# AS1324_imp.net
KiCad netlist of a schematic drawn in EAGLE
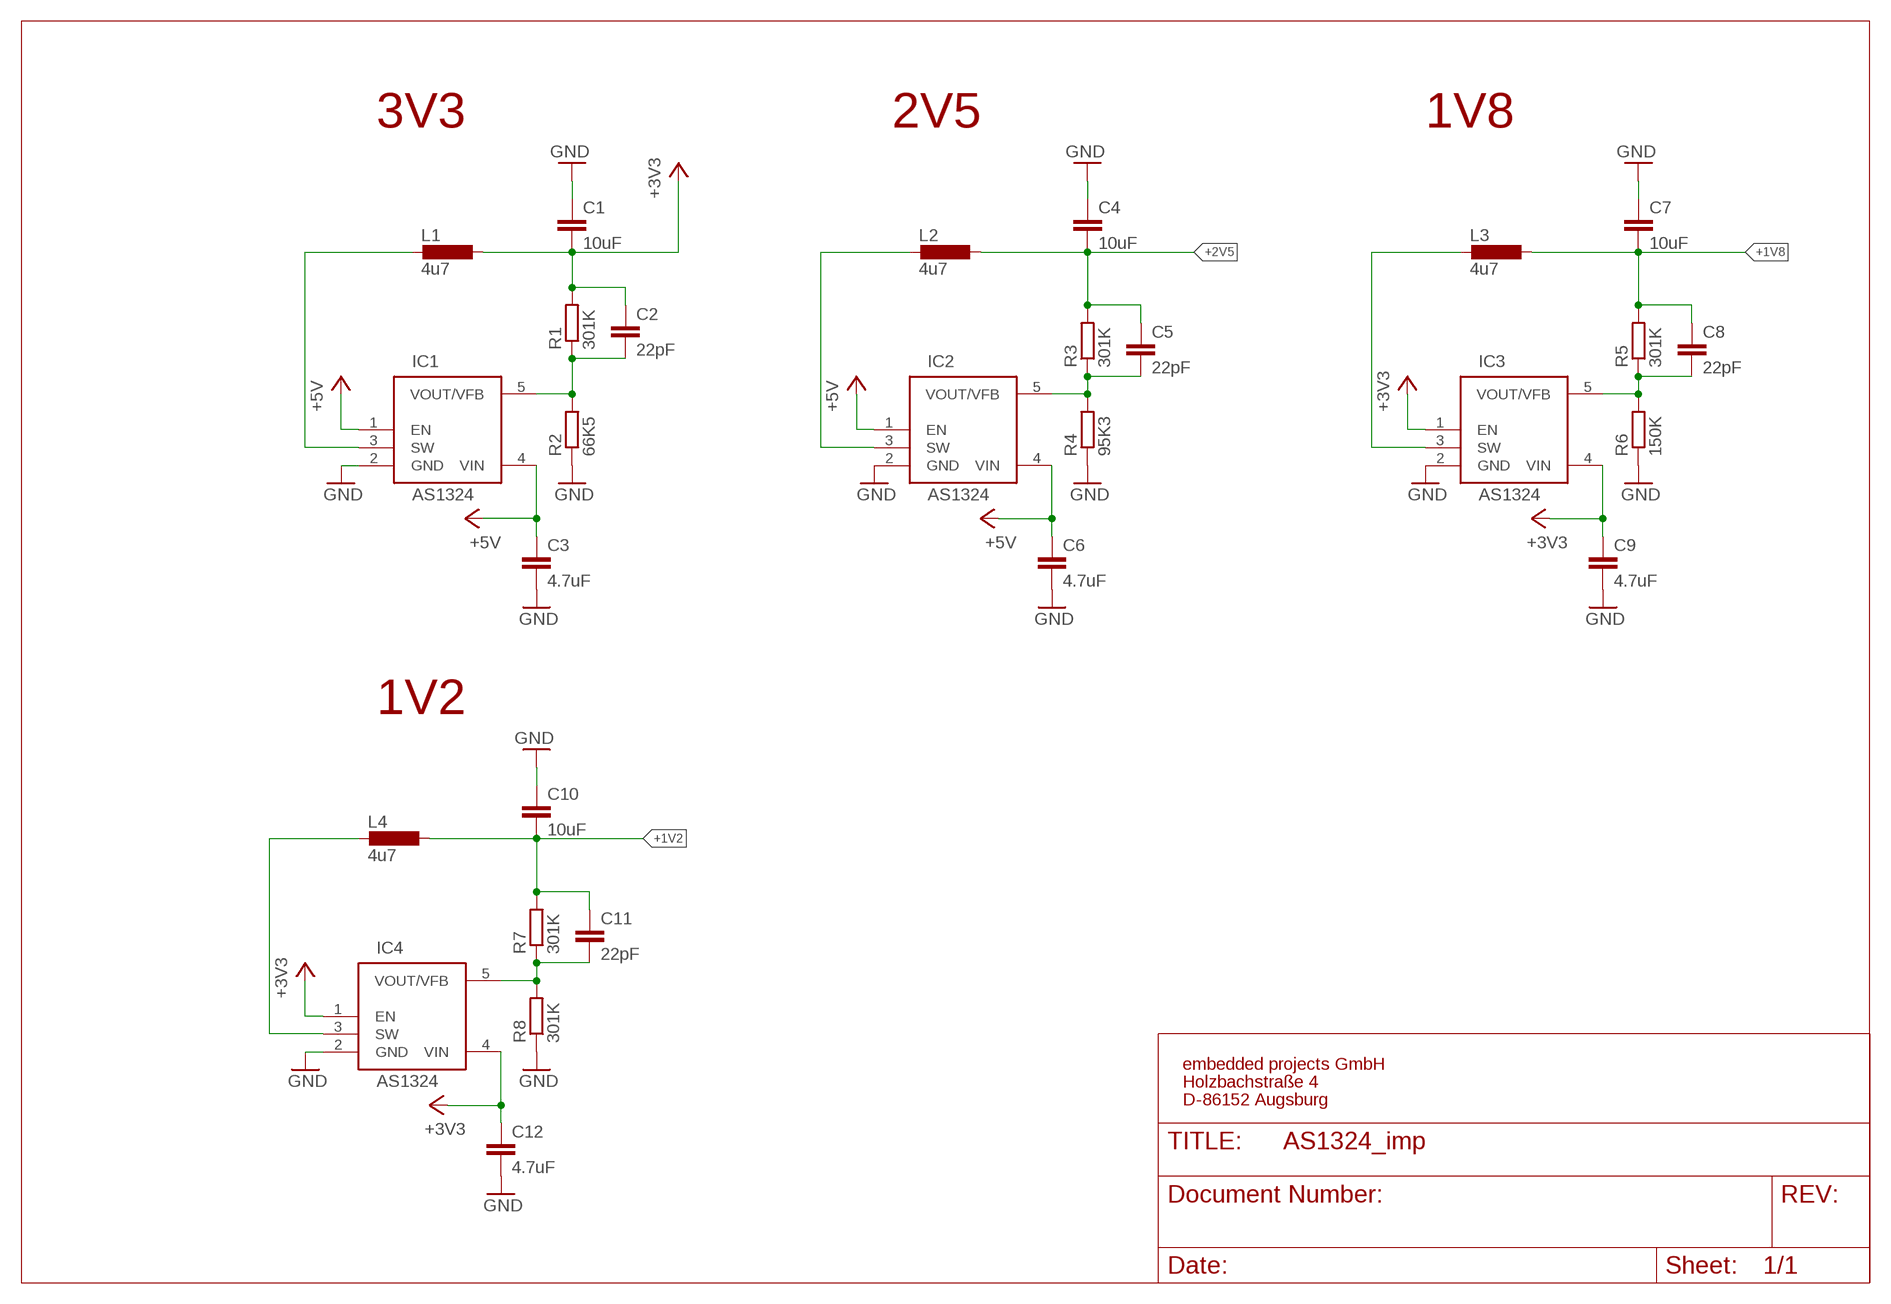
[diagram p0: schematic, sheet 1]

(export (version "E")
  (design (tool "Eeschema 10.0.6"))
  (components
    (comp (ref "C1")
      (value "10uF")
      (footprint "eagle-import:C0805")
      (libsource (lib "eagle-import") (part "C-EUC0805"))
    )
    (comp (ref "C2")
      (value "22pF")
      (footprint "eagle-import:C0805")
      (libsource (lib "eagle-import") (part "C-EUC0805"))
    )
    (comp (ref "C3")
      (value "4.7uF")
      (footprint "eagle-import:C0805")
      (libsource (lib "eagle-import") (part "C-EUC0805"))
    )
    (comp (ref "C4")
      (value "10uF")
      (footprint "eagle-import:C0805")
      (libsource (lib "eagle-import") (part "C-EUC0805"))
    )
    (comp (ref "C5")
      (value "22pF")
      (footprint "eagle-import:C0805")
      (libsource (lib "eagle-import") (part "C-EUC0805"))
    )
    (comp (ref "C6")
      (value "4.7uF")
      (footprint "eagle-import:C0805")
      (libsource (lib "eagle-import") (part "C-EUC0805"))
    )
    (comp (ref "C7")
      (value "10uF")
      (footprint "eagle-import:C0805")
      (libsource (lib "eagle-import") (part "C-EUC0805"))
    )
    (comp (ref "C8")
      (value "22pF")
      (footprint "eagle-import:C0805")
      (libsource (lib "eagle-import") (part "C-EUC0805"))
    )
    (comp (ref "C9")
      (value "4.7uF")
      (footprint "eagle-import:C0805")
      (libsource (lib "eagle-import") (part "C-EUC0805"))
    )
    (comp (ref "C10")
      (value "10uF")
      (footprint "eagle-import:C0805")
      (libsource (lib "eagle-import") (part "C-EUC0805"))
    )
    (comp (ref "C11")
      (value "22pF")
      (footprint "eagle-import:C0805")
      (libsource (lib "eagle-import") (part "C-EUC0805"))
    )
    (comp (ref "C12")
      (value "4.7uF")
      (footprint "eagle-import:C0805")
      (libsource (lib "eagle-import") (part "C-EUC0805"))
    )
    (comp (ref "IC1")
      (value "AS1324")
      (footprint "eagle-import:TSOT23")
      (libsource (lib "eagle-import") (part "AS1324"))
    )
    (comp (ref "IC2")
      (value "AS1324")
      (footprint "eagle-import:TSOT23")
      (libsource (lib "eagle-import") (part "AS1324"))
    )
    (comp (ref "IC3")
      (value "AS1324")
      (footprint "eagle-import:TSOT23")
      (libsource (lib "eagle-import") (part "AS1324"))
    )
    (comp (ref "IC4")
      (value "AS1324")
      (footprint "eagle-import:TSOT23")
      (libsource (lib "eagle-import") (part "AS1324"))
    )
    (comp (ref "L1")
      (value "4u7")
      (footprint "eagle-import:PSU3014")
      (libsource (lib "eagle-import") (part "PSU3014"))
    )
    (comp (ref "L2")
      (value "4u7")
      (footprint "eagle-import:PSU3014")
      (libsource (lib "eagle-import") (part "PSU3014"))
    )
    (comp (ref "L3")
      (value "4u7")
      (footprint "eagle-import:PSU3014")
      (libsource (lib "eagle-import") (part "PSU3014"))
    )
    (comp (ref "L4")
      (value "4u7")
      (footprint "eagle-import:PSU3014")
      (libsource (lib "eagle-import") (part "PSU3014"))
    )
    (comp (ref "R1")
      (value "301K")
      (footprint "eagle-import:R0805")
      (libsource (lib "eagle-import") (part "R-EU_R0805"))
    )
    (comp (ref "R2")
      (value "66K5")
      (footprint "eagle-import:R0805")
      (libsource (lib "eagle-import") (part "R-EU_R0805"))
    )
    (comp (ref "R3")
      (value "301K")
      (footprint "eagle-import:R0805")
      (libsource (lib "eagle-import") (part "R-EU_R0805"))
    )
    (comp (ref "R4")
      (value "95K3")
      (footprint "eagle-import:R0805")
      (libsource (lib "eagle-import") (part "R-EU_R0805"))
    )
    (comp (ref "R5")
      (value "301K")
      (footprint "eagle-import:R0805")
      (libsource (lib "eagle-import") (part "R-EU_R0805"))
    )
    (comp (ref "R6")
      (value "150K")
      (footprint "eagle-import:R0805")
      (libsource (lib "eagle-import") (part "R-EU_R0805"))
    )
    (comp (ref "R7")
      (value "301K")
      (footprint "eagle-import:R0805")
      (libsource (lib "eagle-import") (part "R-EU_R0805"))
    )
    (comp (ref "R8")
      (value "301K")
      (footprint "eagle-import:R0805")
      (libsource (lib "eagle-import") (part "R-EU_R0805"))
    )
  )
  (nets
    (net (code "1") (name "+1V2") (class "Default")
      (node (ref "C10") (pin "2") (pinfunction "2_2") (pintype "passive"))
      (node (ref "C11") (pin "1") (pinfunction "1_1") (pintype "passive"))
      (node (ref "L4") (pin "2") (pinfunction "2_2") (pintype "passive"))
      (node (ref "R7") (pin "2") (pinfunction "2_2") (pintype "passive"))
    )
    (net (code "2") (name "+1V8") (class "Default")
      (node (ref "C7") (pin "2") (pinfunction "2_2") (pintype "passive"))
      (node (ref "C8") (pin "1") (pinfunction "1_1") (pintype "passive"))
      (node (ref "L3") (pin "2") (pinfunction "2_2") (pintype "passive"))
      (node (ref "R5") (pin "2") (pinfunction "2_2") (pintype "passive"))
    )
    (net (code "3") (name "+2V5") (class "Default")
      (node (ref "C4") (pin "2") (pinfunction "2_2") (pintype "passive"))
      (node (ref "C5") (pin "1") (pinfunction "1_1") (pintype "passive"))
      (node (ref "L2") (pin "2") (pinfunction "2_2") (pintype "passive"))
      (node (ref "R3") (pin "2") (pinfunction "2_2") (pintype "passive"))
    )
    (net (code "4") (name "+3V3") (class "Default")
      (node (ref "C1") (pin "2") (pinfunction "2_2") (pintype "passive"))
      (node (ref "C12") (pin "1") (pinfunction "1_1") (pintype "passive"))
      (node (ref "C2") (pin "1") (pinfunction "1_1") (pintype "passive"))
      (node (ref "C9") (pin "1") (pinfunction "1_1") (pintype "passive"))
      (node (ref "IC3") (pin "1") (pinfunction "EN_1") (pintype "bidirectional"))
      (node (ref "IC3") (pin "4") (pinfunction "VIN_4") (pintype "bidirectional"))
      (node (ref "IC4") (pin "1") (pinfunction "EN_1") (pintype "bidirectional"))
      (node (ref "IC4") (pin "4") (pinfunction "VIN_4") (pintype "bidirectional"))
      (node (ref "L1") (pin "2") (pinfunction "2_2") (pintype "passive"))
      (node (ref "R1") (pin "2") (pinfunction "2_2") (pintype "passive"))
    )
    (net (code "5") (name "+5V") (class "Default")
      (node (ref "C3") (pin "1") (pinfunction "1_1") (pintype "passive"))
      (node (ref "C6") (pin "1") (pinfunction "1_1") (pintype "passive"))
      (node (ref "IC1") (pin "1") (pinfunction "EN_1") (pintype "bidirectional"))
      (node (ref "IC1") (pin "4") (pinfunction "VIN_4") (pintype "bidirectional"))
      (node (ref "IC2") (pin "1") (pinfunction "EN_1") (pintype "bidirectional"))
      (node (ref "IC2") (pin "4") (pinfunction "VIN_4") (pintype "bidirectional"))
    )
    (net (code "6") (name "GND") (class "Default")
      (node (ref "C1") (pin "1") (pinfunction "1_1") (pintype "passive"))
      (node (ref "C10") (pin "1") (pinfunction "1_1") (pintype "passive"))
      (node (ref "C12") (pin "2") (pinfunction "2_2") (pintype "passive"))
      (node (ref "C3") (pin "2") (pinfunction "2_2") (pintype "passive"))
      (node (ref "C4") (pin "1") (pinfunction "1_1") (pintype "passive"))
      (node (ref "C6") (pin "2") (pinfunction "2_2") (pintype "passive"))
      (node (ref "C7") (pin "1") (pinfunction "1_1") (pintype "passive"))
      (node (ref "C9") (pin "2") (pinfunction "2_2") (pintype "passive"))
      (node (ref "IC1") (pin "2") (pinfunction "GND_2") (pintype "bidirectional"))
      (node (ref "IC2") (pin "2") (pinfunction "GND_2") (pintype "bidirectional"))
      (node (ref "IC3") (pin "2") (pinfunction "GND_2") (pintype "bidirectional"))
      (node (ref "IC4") (pin "2") (pinfunction "GND_2") (pintype "bidirectional"))
      (node (ref "R2") (pin "1") (pinfunction "1_1") (pintype "passive"))
      (node (ref "R4") (pin "1") (pinfunction "1_1") (pintype "passive"))
      (node (ref "R6") (pin "1") (pinfunction "1_1") (pintype "passive"))
      (node (ref "R8") (pin "1") (pinfunction "1_1") (pintype "passive"))
    )
    (net (code "7") (name "Net-(IC1-SW)") (class "Default")
      (node (ref "IC1") (pin "3") (pinfunction "SW_3") (pintype "bidirectional"))
      (node (ref "L1") (pin "1") (pinfunction "1_1") (pintype "passive"))
    )
    (net (code "8") (name "Net-(IC1-VOUT{slash}VFB)") (class "Default")
      (node (ref "C2") (pin "2") (pinfunction "2_2") (pintype "passive"))
      (node (ref "IC1") (pin "5") (pinfunction "VOUT/VFB_5") (pintype "bidirectional"))
      (node (ref "R1") (pin "1") (pinfunction "1_1") (pintype "passive"))
      (node (ref "R2") (pin "2") (pinfunction "2_2") (pintype "passive"))
    )
    (net (code "9") (name "Net-(IC2-SW)") (class "Default")
      (node (ref "IC2") (pin "3") (pinfunction "SW_3") (pintype "bidirectional"))
      (node (ref "L2") (pin "1") (pinfunction "1_1") (pintype "passive"))
    )
    (net (code "10") (name "Net-(IC2-VOUT{slash}VFB)") (class "Default")
      (node (ref "C5") (pin "2") (pinfunction "2_2") (pintype "passive"))
      (node (ref "IC2") (pin "5") (pinfunction "VOUT/VFB_5") (pintype "bidirectional"))
      (node (ref "R3") (pin "1") (pinfunction "1_1") (pintype "passive"))
      (node (ref "R4") (pin "2") (pinfunction "2_2") (pintype "passive"))
    )
    (net (code "11") (name "Net-(IC3-SW)") (class "Default")
      (node (ref "IC3") (pin "3") (pinfunction "SW_3") (pintype "bidirectional"))
      (node (ref "L3") (pin "1") (pinfunction "1_1") (pintype "passive"))
    )
    (net (code "12") (name "Net-(IC3-VOUT{slash}VFB)") (class "Default")
      (node (ref "C8") (pin "2") (pinfunction "2_2") (pintype "passive"))
      (node (ref "IC3") (pin "5") (pinfunction "VOUT/VFB_5") (pintype "bidirectional"))
      (node (ref "R5") (pin "1") (pinfunction "1_1") (pintype "passive"))
      (node (ref "R6") (pin "2") (pinfunction "2_2") (pintype "passive"))
    )
    (net (code "13") (name "Net-(IC4-SW)") (class "Default")
      (node (ref "IC4") (pin "3") (pinfunction "SW_3") (pintype "bidirectional"))
      (node (ref "L4") (pin "1") (pinfunction "1_1") (pintype "passive"))
    )
    (net (code "14") (name "Net-(IC4-VOUT{slash}VFB)") (class "Default")
      (node (ref "C11") (pin "2") (pinfunction "2_2") (pintype "passive"))
      (node (ref "IC4") (pin "5") (pinfunction "VOUT/VFB_5") (pintype "bidirectional"))
      (node (ref "R7") (pin "1") (pinfunction "1_1") (pintype "passive"))
      (node (ref "R8") (pin "2") (pinfunction "2_2") (pintype "passive"))
    )
  )
)
